# YF-Buzzer.net
KiCad netlist of a schematic drawn in EAGLE
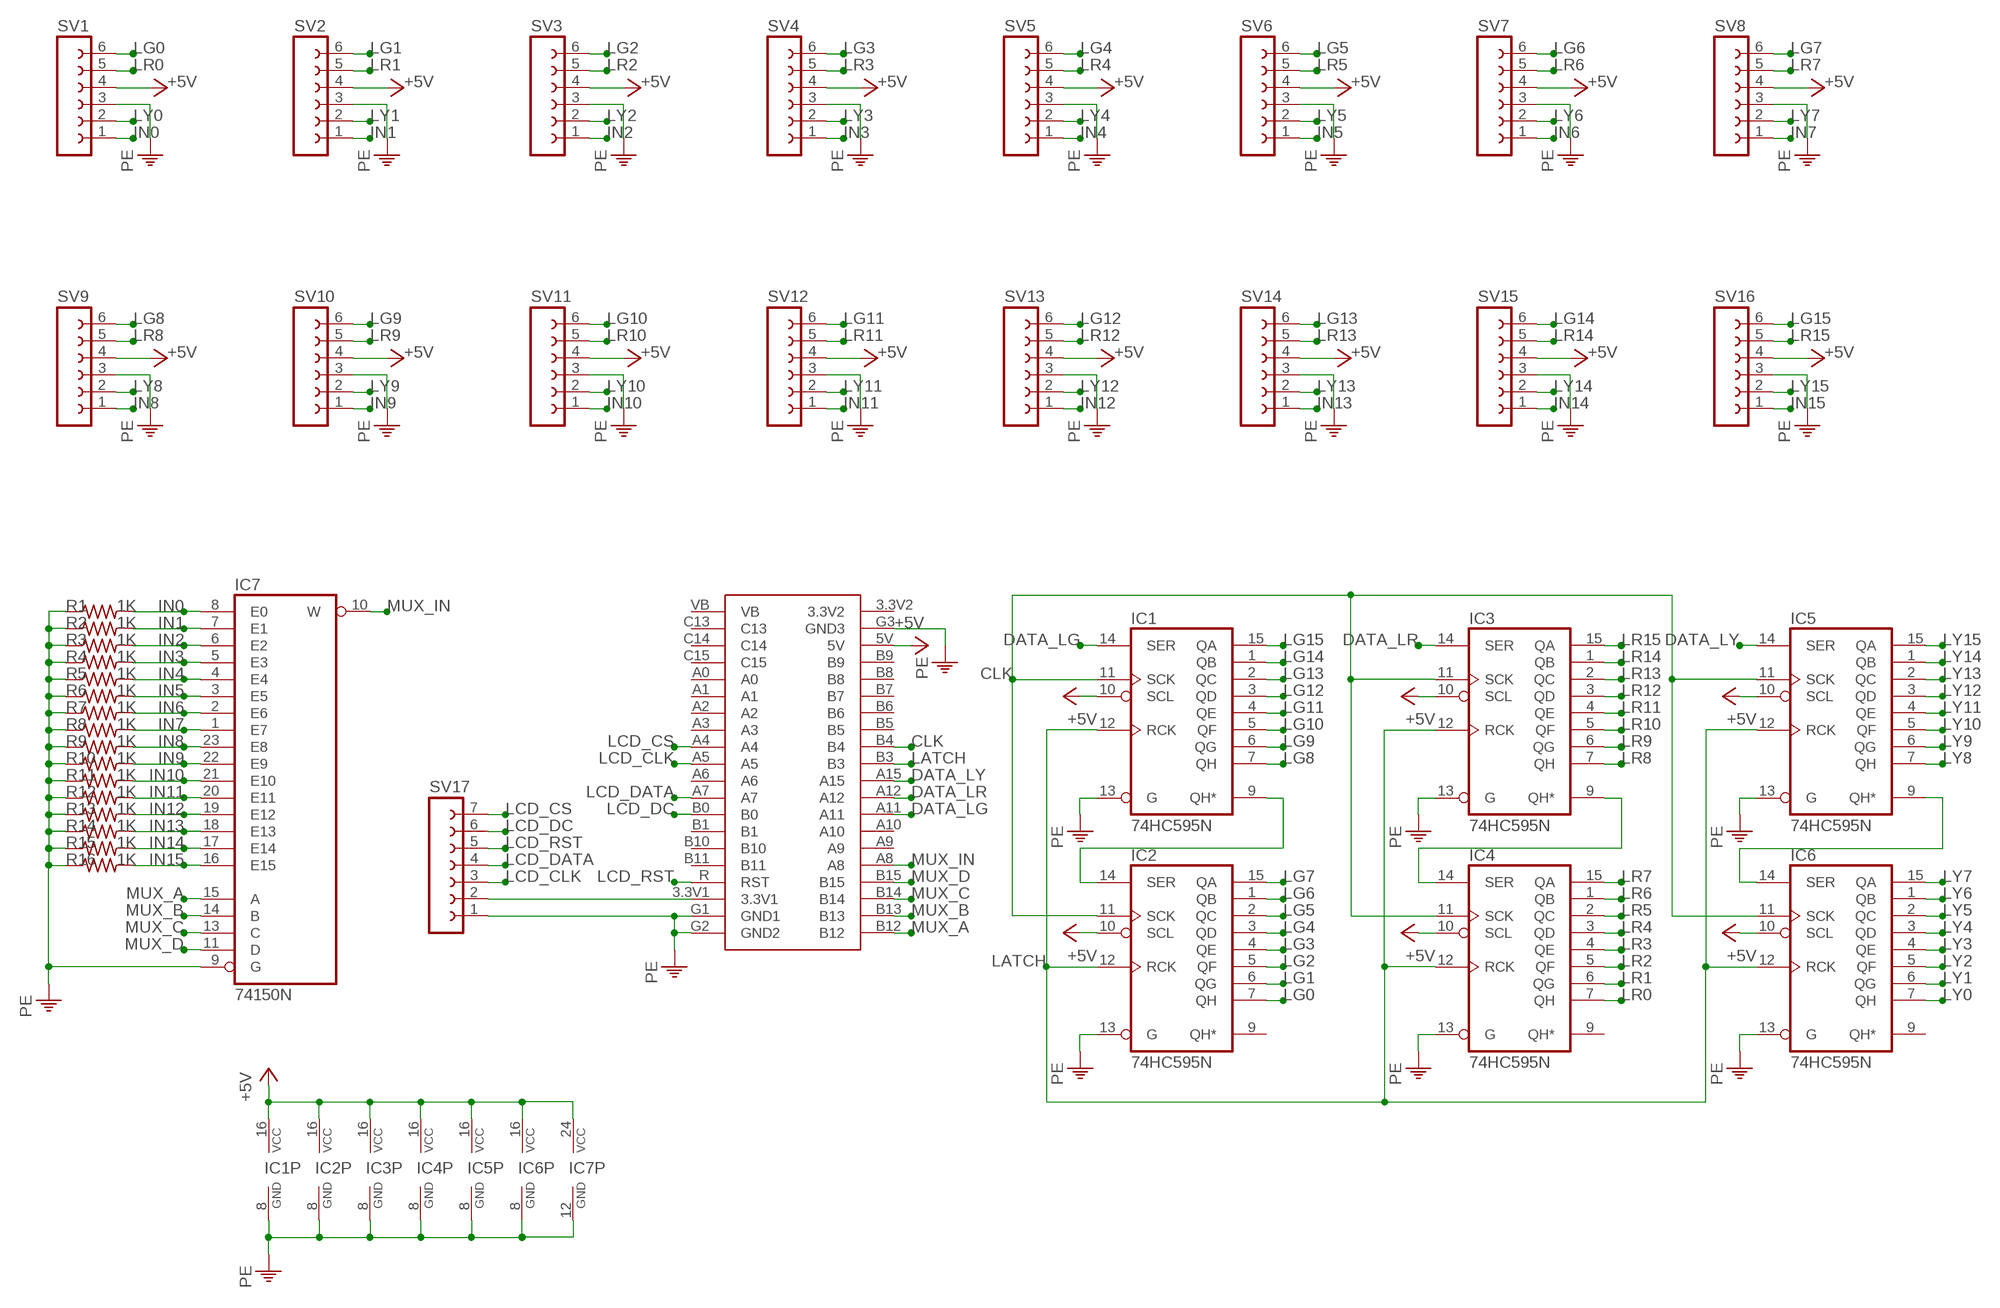
[diagram p0: schematic, sheet 1]

(export (version "E")
  (design (tool "Eeschema 10.0.6"))
  (components
    (comp (ref "IC1")
      (value "74HC595N")
      (footprint "eagle-import:DIL16")
      (libsource (lib "eagle-import") (part "74595NHC"))
    )
    (comp (ref "IC2")
      (value "74HC595N")
      (footprint "eagle-import:DIL16")
      (libsource (lib "eagle-import") (part "74595NHC"))
    )
    (comp (ref "IC3")
      (value "74HC595N")
      (footprint "eagle-import:DIL16")
      (libsource (lib "eagle-import") (part "74595NHC"))
    )
    (comp (ref "IC4")
      (value "74HC595N")
      (footprint "eagle-import:DIL16")
      (libsource (lib "eagle-import") (part "74595NHC"))
    )
    (comp (ref "IC5")
      (value "74HC595N")
      (footprint "eagle-import:DIL16")
      (libsource (lib "eagle-import") (part "74595NHC"))
    )
    (comp (ref "IC6")
      (value "74HC595N")
      (footprint "eagle-import:DIL16")
      (libsource (lib "eagle-import") (part "74595NHC"))
    )
    (comp (ref "IC7")
      (value "74150N")
      (footprint "eagle-import:DIL24-6")
      (libsource (lib "eagle-import") (part "74150N"))
    )
    (comp (ref "MCU1")
      (value "STM32-BLUE")
      (footprint "eagle-import:STM32-BLUE")
      (libsource (lib "eagle-import") (part "STM32-BLUE"))
    )
    (comp (ref "R1")
      (value "1K")
      (footprint "eagle-import:0207_10")
      (libsource (lib "eagle-import") (part "R-US_0207/10"))
    )
    (comp (ref "R2")
      (value "1K")
      (footprint "eagle-import:0207_10")
      (libsource (lib "eagle-import") (part "R-US_0207/10"))
    )
    (comp (ref "R3")
      (value "1K")
      (footprint "eagle-import:0207_10")
      (libsource (lib "eagle-import") (part "R-US_0207/10"))
    )
    (comp (ref "R4")
      (value "1K")
      (footprint "eagle-import:0207_10")
      (libsource (lib "eagle-import") (part "R-US_0207/10"))
    )
    (comp (ref "R5")
      (value "1K")
      (footprint "eagle-import:0207_10")
      (libsource (lib "eagle-import") (part "R-US_0207/10"))
    )
    (comp (ref "R6")
      (value "1K")
      (footprint "eagle-import:0207_10")
      (libsource (lib "eagle-import") (part "R-US_0207/10"))
    )
    (comp (ref "R7")
      (value "1K")
      (footprint "eagle-import:0207_10")
      (libsource (lib "eagle-import") (part "R-US_0207/10"))
    )
    (comp (ref "R8")
      (value "1K")
      (footprint "eagle-import:0207_10")
      (libsource (lib "eagle-import") (part "R-US_0207/10"))
    )
    (comp (ref "R9")
      (value "1K")
      (footprint "eagle-import:0207_10")
      (libsource (lib "eagle-import") (part "R-US_0207/10"))
    )
    (comp (ref "R10")
      (value "1K")
      (footprint "eagle-import:0207_10")
      (libsource (lib "eagle-import") (part "R-US_0207/10"))
    )
    (comp (ref "R11")
      (value "1K")
      (footprint "eagle-import:0207_10")
      (libsource (lib "eagle-import") (part "R-US_0207/10"))
    )
    (comp (ref "R12")
      (value "1K")
      (footprint "eagle-import:0207_10")
      (libsource (lib "eagle-import") (part "R-US_0207/10"))
    )
    (comp (ref "R13")
      (value "1K")
      (footprint "eagle-import:0207_10")
      (libsource (lib "eagle-import") (part "R-US_0207/10"))
    )
    (comp (ref "R14")
      (value "1K")
      (footprint "eagle-import:0207_10")
      (libsource (lib "eagle-import") (part "R-US_0207/10"))
    )
    (comp (ref "R15")
      (value "1K")
      (footprint "eagle-import:0207_10")
      (libsource (lib "eagle-import") (part "R-US_0207/10"))
    )
    (comp (ref "R16")
      (value "1K")
      (footprint "eagle-import:0207_10")
      (libsource (lib "eagle-import") (part "R-US_0207/10"))
    )
    (comp (ref "SV1")
      (value "FE06-1")
      (footprint "eagle-import:FE06")
      (libsource (lib "eagle-import") (part "FE06-1"))
    )
    (comp (ref "SV2")
      (value "FE06-1")
      (footprint "eagle-import:FE06")
      (libsource (lib "eagle-import") (part "FE06-1"))
    )
    (comp (ref "SV3")
      (value "FE06-1")
      (footprint "eagle-import:FE06")
      (libsource (lib "eagle-import") (part "FE06-1"))
    )
    (comp (ref "SV4")
      (value "FE06-1")
      (footprint "eagle-import:FE06")
      (libsource (lib "eagle-import") (part "FE06-1"))
    )
    (comp (ref "SV5")
      (value "FE06-1")
      (footprint "eagle-import:FE06")
      (libsource (lib "eagle-import") (part "FE06-1"))
    )
    (comp (ref "SV6")
      (value "FE06-1")
      (footprint "eagle-import:FE06")
      (libsource (lib "eagle-import") (part "FE06-1"))
    )
    (comp (ref "SV7")
      (value "FE06-1")
      (footprint "eagle-import:FE06")
      (libsource (lib "eagle-import") (part "FE06-1"))
    )
    (comp (ref "SV8")
      (value "FE06-1")
      (footprint "eagle-import:FE06")
      (libsource (lib "eagle-import") (part "FE06-1"))
    )
    (comp (ref "SV9")
      (value "FE06-1")
      (footprint "eagle-import:FE06")
      (libsource (lib "eagle-import") (part "FE06-1"))
    )
    (comp (ref "SV10")
      (value "FE06-1")
      (footprint "eagle-import:FE06")
      (libsource (lib "eagle-import") (part "FE06-1"))
    )
    (comp (ref "SV11")
      (value "FE06-1")
      (footprint "eagle-import:FE06")
      (libsource (lib "eagle-import") (part "FE06-1"))
    )
    (comp (ref "SV12")
      (value "FE06-1")
      (footprint "eagle-import:FE06")
      (libsource (lib "eagle-import") (part "FE06-1"))
    )
    (comp (ref "SV13")
      (value "FE06-1")
      (footprint "eagle-import:FE06")
      (libsource (lib "eagle-import") (part "FE06-1"))
    )
    (comp (ref "SV14")
      (value "FE06-1")
      (footprint "eagle-import:FE06")
      (libsource (lib "eagle-import") (part "FE06-1"))
    )
    (comp (ref "SV15")
      (value "FE06-1")
      (footprint "eagle-import:FE06")
      (libsource (lib "eagle-import") (part "FE06-1"))
    )
    (comp (ref "SV16")
      (value "FE06-1")
      (footprint "eagle-import:FE06")
      (libsource (lib "eagle-import") (part "FE06-1"))
    )
    (comp (ref "SV17")
      (value "FE07-1")
      (footprint "eagle-import:FE07")
      (libsource (lib "eagle-import") (part "FE07-1"))
    )
  )
  (nets
    (net (code "1") (name "+5V") (class "Default")
      (node (ref "IC1") (pin "10") (pinfunction "SCL_10") (pintype "input"))
      (node (ref "IC1") (pin "16") (pinfunction "VCC_16") (pintype "power_in"))
      (node (ref "IC2") (pin "10") (pinfunction "SCL_10") (pintype "input"))
      (node (ref "IC2") (pin "16") (pinfunction "VCC_16") (pintype "power_in"))
      (node (ref "IC3") (pin "10") (pinfunction "SCL_10") (pintype "input"))
      (node (ref "IC3") (pin "16") (pinfunction "VCC_16") (pintype "power_in"))
      (node (ref "IC4") (pin "10") (pinfunction "SCL_10") (pintype "input"))
      (node (ref "IC4") (pin "16") (pinfunction "VCC_16") (pintype "power_in"))
      (node (ref "IC5") (pin "10") (pinfunction "SCL_10") (pintype "input"))
      (node (ref "IC5") (pin "16") (pinfunction "VCC_16") (pintype "power_in"))
      (node (ref "IC6") (pin "10") (pinfunction "SCL_10") (pintype "input"))
      (node (ref "IC6") (pin "16") (pinfunction "VCC_16") (pintype "power_in"))
      (node (ref "IC7") (pin "24") (pinfunction "VCC_24") (pintype "power_in"))
      (node (ref "MCU1") (pin "5V") (pinfunction "5V_5V") (pintype "power_in"))
      (node (ref "SV1") (pin "4") (pinfunction "4_4") (pintype "passive"))
      (node (ref "SV10") (pin "4") (pinfunction "4_4") (pintype "passive"))
      (node (ref "SV11") (pin "4") (pinfunction "4_4") (pintype "passive"))
      (node (ref "SV12") (pin "4") (pinfunction "4_4") (pintype "passive"))
      (node (ref "SV13") (pin "4") (pinfunction "4_4") (pintype "passive"))
      (node (ref "SV14") (pin "4") (pinfunction "4_4") (pintype "passive"))
      (node (ref "SV15") (pin "4") (pinfunction "4_4") (pintype "passive"))
      (node (ref "SV16") (pin "4") (pinfunction "4_4") (pintype "passive"))
      (node (ref "SV2") (pin "4") (pinfunction "4_4") (pintype "passive"))
      (node (ref "SV3") (pin "4") (pinfunction "4_4") (pintype "passive"))
      (node (ref "SV4") (pin "4") (pinfunction "4_4") (pintype "passive"))
      (node (ref "SV5") (pin "4") (pinfunction "4_4") (pintype "passive"))
      (node (ref "SV6") (pin "4") (pinfunction "4_4") (pintype "passive"))
      (node (ref "SV7") (pin "4") (pinfunction "4_4") (pintype "passive"))
      (node (ref "SV8") (pin "4") (pinfunction "4_4") (pintype "passive"))
      (node (ref "SV9") (pin "4") (pinfunction "4_4") (pintype "passive"))
    )
    (net (code "2") (name "/3.3V2") (class "Default")
      (node (ref "MCU1") (pin "3.3V2") (pinfunction "3.3V2_3.3V2") (pintype "power_in"))
    )
    (net (code "3") (name "/CLK") (class "Default")
      (node (ref "IC1") (pin "11") (pinfunction "SCK_11") (pintype "input"))
      (node (ref "IC2") (pin "11") (pinfunction "SCK_11") (pintype "input"))
      (node (ref "IC3") (pin "11") (pinfunction "SCK_11") (pintype "input"))
      (node (ref "IC4") (pin "11") (pinfunction "SCK_11") (pintype "input"))
      (node (ref "IC5") (pin "11") (pinfunction "SCK_11") (pintype "input"))
      (node (ref "IC6") (pin "11") (pinfunction "SCK_11") (pintype "input"))
      (node (ref "MCU1") (pin "B4") (pinfunction "B4_B4") (pintype "bidirectional"))
    )
    (net (code "4") (name "/DATA_LG") (class "Default")
      (node (ref "IC1") (pin "14") (pinfunction "SER_14") (pintype "input"))
      (node (ref "MCU1") (pin "A11") (pinfunction "A11_A11") (pintype "bidirectional"))
    )
    (net (code "5") (name "/DATA_LR") (class "Default")
      (node (ref "IC3") (pin "14") (pinfunction "SER_14") (pintype "input"))
      (node (ref "MCU1") (pin "A12") (pinfunction "A12_A12") (pintype "bidirectional"))
    )
    (net (code "6") (name "/DATA_LY") (class "Default")
      (node (ref "IC5") (pin "14") (pinfunction "SER_14") (pintype "input"))
      (node (ref "MCU1") (pin "A15") (pinfunction "A15_A15") (pintype "bidirectional"))
    )
    (net (code "7") (name "/IN0") (class "Default")
      (node (ref "IC7") (pin "8") (pinfunction "E0_8") (pintype "input"))
      (node (ref "R1") (pin "2") (pinfunction "2_2") (pintype "passive"))
      (node (ref "SV1") (pin "1") (pinfunction "1_1") (pintype "passive"))
    )
    (net (code "8") (name "/IN1") (class "Default")
      (node (ref "IC7") (pin "7") (pinfunction "E1_7") (pintype "input"))
      (node (ref "R2") (pin "2") (pinfunction "2_2") (pintype "passive"))
      (node (ref "SV2") (pin "1") (pinfunction "1_1") (pintype "passive"))
    )
    (net (code "9") (name "/IN2") (class "Default")
      (node (ref "IC7") (pin "6") (pinfunction "E2_6") (pintype "input"))
      (node (ref "R3") (pin "2") (pinfunction "2_2") (pintype "passive"))
      (node (ref "SV3") (pin "1") (pinfunction "1_1") (pintype "passive"))
    )
    (net (code "10") (name "/IN3") (class "Default")
      (node (ref "IC7") (pin "5") (pinfunction "E3_5") (pintype "input"))
      (node (ref "R4") (pin "2") (pinfunction "2_2") (pintype "passive"))
      (node (ref "SV4") (pin "1") (pinfunction "1_1") (pintype "passive"))
    )
    (net (code "11") (name "/IN4") (class "Default")
      (node (ref "IC7") (pin "4") (pinfunction "E4_4") (pintype "input"))
      (node (ref "R5") (pin "2") (pinfunction "2_2") (pintype "passive"))
      (node (ref "SV5") (pin "1") (pinfunction "1_1") (pintype "passive"))
    )
    (net (code "12") (name "/IN5") (class "Default")
      (node (ref "IC7") (pin "3") (pinfunction "E5_3") (pintype "input"))
      (node (ref "R6") (pin "2") (pinfunction "2_2") (pintype "passive"))
      (node (ref "SV6") (pin "1") (pinfunction "1_1") (pintype "passive"))
    )
    (net (code "13") (name "/IN6") (class "Default")
      (node (ref "IC7") (pin "2") (pinfunction "E6_2") (pintype "input"))
      (node (ref "R7") (pin "2") (pinfunction "2_2") (pintype "passive"))
      (node (ref "SV7") (pin "1") (pinfunction "1_1") (pintype "passive"))
    )
    (net (code "14") (name "/IN7") (class "Default")
      (node (ref "IC7") (pin "1") (pinfunction "E7_1") (pintype "input"))
      (node (ref "R8") (pin "2") (pinfunction "2_2") (pintype "passive"))
      (node (ref "SV8") (pin "1") (pinfunction "1_1") (pintype "passive"))
    )
    (net (code "15") (name "/IN8") (class "Default")
      (node (ref "IC7") (pin "23") (pinfunction "E8_23") (pintype "input"))
      (node (ref "R9") (pin "2") (pinfunction "2_2") (pintype "passive"))
      (node (ref "SV9") (pin "1") (pinfunction "1_1") (pintype "passive"))
    )
    (net (code "16") (name "/IN9") (class "Default")
      (node (ref "IC7") (pin "22") (pinfunction "E9_22") (pintype "input"))
      (node (ref "R10") (pin "2") (pinfunction "2_2") (pintype "passive"))
      (node (ref "SV10") (pin "1") (pinfunction "1_1") (pintype "passive"))
    )
    (net (code "17") (name "/IN10") (class "Default")
      (node (ref "IC7") (pin "21") (pinfunction "E10_21") (pintype "input"))
      (node (ref "R11") (pin "2") (pinfunction "2_2") (pintype "passive"))
      (node (ref "SV11") (pin "1") (pinfunction "1_1") (pintype "passive"))
    )
    (net (code "18") (name "/IN11") (class "Default")
      (node (ref "IC7") (pin "20") (pinfunction "E11_20") (pintype "input"))
      (node (ref "R12") (pin "2") (pinfunction "2_2") (pintype "passive"))
      (node (ref "SV12") (pin "1") (pinfunction "1_1") (pintype "passive"))
    )
    (net (code "19") (name "/IN12") (class "Default")
      (node (ref "IC7") (pin "19") (pinfunction "E12_19") (pintype "input"))
      (node (ref "R13") (pin "2") (pinfunction "2_2") (pintype "passive"))
      (node (ref "SV13") (pin "1") (pinfunction "1_1") (pintype "passive"))
    )
    (net (code "20") (name "/IN13") (class "Default")
      (node (ref "IC7") (pin "18") (pinfunction "E13_18") (pintype "input"))
      (node (ref "R14") (pin "2") (pinfunction "2_2") (pintype "passive"))
      (node (ref "SV14") (pin "1") (pinfunction "1_1") (pintype "passive"))
    )
    (net (code "21") (name "/IN14") (class "Default")
      (node (ref "IC7") (pin "17") (pinfunction "E14_17") (pintype "input"))
      (node (ref "R15") (pin "2") (pinfunction "2_2") (pintype "passive"))
      (node (ref "SV15") (pin "1") (pinfunction "1_1") (pintype "passive"))
    )
    (net (code "22") (name "/IN15") (class "Default")
      (node (ref "IC7") (pin "16") (pinfunction "E15_16") (pintype "input"))
      (node (ref "R16") (pin "2") (pinfunction "2_2") (pintype "passive"))
      (node (ref "SV16") (pin "1") (pinfunction "1_1") (pintype "passive"))
    )
    (net (code "23") (name "/LATCH") (class "Default")
      (node (ref "IC1") (pin "12") (pinfunction "RCK_12") (pintype "input"))
      (node (ref "IC2") (pin "12") (pinfunction "RCK_12") (pintype "input"))
      (node (ref "IC3") (pin "12") (pinfunction "RCK_12") (pintype "input"))
      (node (ref "IC4") (pin "12") (pinfunction "RCK_12") (pintype "input"))
      (node (ref "IC5") (pin "12") (pinfunction "RCK_12") (pintype "input"))
      (node (ref "IC6") (pin "12") (pinfunction "RCK_12") (pintype "input"))
      (node (ref "MCU1") (pin "B3") (pinfunction "B3_B3") (pintype "bidirectional"))
    )
    (net (code "24") (name "/LCD_CLK") (class "Default")
      (node (ref "MCU1") (pin "A5") (pinfunction "A5_A5") (pintype "bidirectional"))
      (node (ref "SV17") (pin "3") (pinfunction "3_3") (pintype "passive"))
    )
    (net (code "25") (name "/LCD_CS") (class "Default")
      (node (ref "MCU1") (pin "A4") (pinfunction "A4_A4") (pintype "bidirectional"))
      (node (ref "SV17") (pin "7") (pinfunction "7_7") (pintype "passive"))
    )
    (net (code "26") (name "/LCD_DATA") (class "Default")
      (node (ref "MCU1") (pin "A7") (pinfunction "A7_A7") (pintype "bidirectional"))
      (node (ref "SV17") (pin "4") (pinfunction "4_4") (pintype "passive"))
    )
    (net (code "27") (name "/LCD_DC") (class "Default")
      (node (ref "MCU1") (pin "B0") (pinfunction "B0_B0") (pintype "bidirectional"))
      (node (ref "SV17") (pin "6") (pinfunction "6_6") (pintype "passive"))
    )
    (net (code "28") (name "/LCD_RST") (class "Default")
      (node (ref "MCU1") (pin "R") (pinfunction "RST_R") (pintype "bidirectional"))
      (node (ref "SV17") (pin "5") (pinfunction "5_5") (pintype "passive"))
    )
    (net (code "29") (name "/LG0") (class "Default")
      (node (ref "IC2") (pin "7") (pinfunction "QH_7") (pintype "tri_state"))
      (node (ref "SV1") (pin "6") (pinfunction "6_6") (pintype "passive"))
    )
    (net (code "30") (name "/LG1") (class "Default")
      (node (ref "IC2") (pin "6") (pinfunction "QG_6") (pintype "tri_state"))
      (node (ref "SV2") (pin "6") (pinfunction "6_6") (pintype "passive"))
    )
    (net (code "31") (name "/LG2") (class "Default")
      (node (ref "IC2") (pin "5") (pinfunction "QF_5") (pintype "tri_state"))
      (node (ref "SV3") (pin "6") (pinfunction "6_6") (pintype "passive"))
    )
    (net (code "32") (name "/LG3") (class "Default")
      (node (ref "IC2") (pin "4") (pinfunction "QE_4") (pintype "tri_state"))
      (node (ref "SV4") (pin "6") (pinfunction "6_6") (pintype "passive"))
    )
    (net (code "33") (name "/LG4") (class "Default")
      (node (ref "IC2") (pin "3") (pinfunction "QD_3") (pintype "tri_state"))
      (node (ref "SV5") (pin "6") (pinfunction "6_6") (pintype "passive"))
    )
    (net (code "34") (name "/LG5") (class "Default")
      (node (ref "IC2") (pin "2") (pinfunction "QC_2") (pintype "tri_state"))
      (node (ref "SV6") (pin "6") (pinfunction "6_6") (pintype "passive"))
    )
    (net (code "35") (name "/LG6") (class "Default")
      (node (ref "IC2") (pin "1") (pinfunction "QB_1") (pintype "tri_state"))
      (node (ref "SV7") (pin "6") (pinfunction "6_6") (pintype "passive"))
    )
    (net (code "36") (name "/LG7") (class "Default")
      (node (ref "IC2") (pin "15") (pinfunction "QA_15") (pintype "tri_state"))
      (node (ref "SV8") (pin "6") (pinfunction "6_6") (pintype "passive"))
    )
    (net (code "37") (name "/LG8") (class "Default")
      (node (ref "IC1") (pin "7") (pinfunction "QH_7") (pintype "tri_state"))
      (node (ref "SV9") (pin "6") (pinfunction "6_6") (pintype "passive"))
    )
    (net (code "38") (name "/LG9") (class "Default")
      (node (ref "IC1") (pin "6") (pinfunction "QG_6") (pintype "tri_state"))
      (node (ref "SV10") (pin "6") (pinfunction "6_6") (pintype "passive"))
    )
    (net (code "39") (name "/LG10") (class "Default")
      (node (ref "IC1") (pin "5") (pinfunction "QF_5") (pintype "tri_state"))
      (node (ref "SV11") (pin "6") (pinfunction "6_6") (pintype "passive"))
    )
    (net (code "40") (name "/LG11") (class "Default")
      (node (ref "IC1") (pin "4") (pinfunction "QE_4") (pintype "tri_state"))
      (node (ref "SV12") (pin "6") (pinfunction "6_6") (pintype "passive"))
    )
    (net (code "41") (name "/LG12") (class "Default")
      (node (ref "IC1") (pin "3") (pinfunction "QD_3") (pintype "tri_state"))
      (node (ref "SV13") (pin "6") (pinfunction "6_6") (pintype "passive"))
    )
    (net (code "42") (name "/LG13") (class "Default")
      (node (ref "IC1") (pin "2") (pinfunction "QC_2") (pintype "tri_state"))
      (node (ref "SV14") (pin "6") (pinfunction "6_6") (pintype "passive"))
    )
    (net (code "43") (name "/LG14") (class "Default")
      (node (ref "IC1") (pin "1") (pinfunction "QB_1") (pintype "tri_state"))
      (node (ref "SV15") (pin "6") (pinfunction "6_6") (pintype "passive"))
    )
    (net (code "44") (name "/LG15") (class "Default")
      (node (ref "IC1") (pin "15") (pinfunction "QA_15") (pintype "tri_state"))
      (node (ref "SV16") (pin "6") (pinfunction "6_6") (pintype "passive"))
    )
    (net (code "45") (name "/LR0") (class "Default")
      (node (ref "IC4") (pin "7") (pinfunction "QH_7") (pintype "tri_state"))
      (node (ref "SV1") (pin "5") (pinfunction "5_5") (pintype "passive"))
    )
    (net (code "46") (name "/LR1") (class "Default")
      (node (ref "IC4") (pin "6") (pinfunction "QG_6") (pintype "tri_state"))
      (node (ref "SV2") (pin "5") (pinfunction "5_5") (pintype "passive"))
    )
    (net (code "47") (name "/LR2") (class "Default")
      (node (ref "IC4") (pin "5") (pinfunction "QF_5") (pintype "tri_state"))
      (node (ref "SV3") (pin "5") (pinfunction "5_5") (pintype "passive"))
    )
    (net (code "48") (name "/LR3") (class "Default")
      (node (ref "IC4") (pin "4") (pinfunction "QE_4") (pintype "tri_state"))
      (node (ref "SV4") (pin "5") (pinfunction "5_5") (pintype "passive"))
    )
    (net (code "49") (name "/LR4") (class "Default")
      (node (ref "IC4") (pin "3") (pinfunction "QD_3") (pintype "tri_state"))
      (node (ref "SV5") (pin "5") (pinfunction "5_5") (pintype "passive"))
    )
    (net (code "50") (name "/LR5") (class "Default")
      (node (ref "IC4") (pin "2") (pinfunction "QC_2") (pintype "tri_state"))
      (node (ref "SV6") (pin "5") (pinfunction "5_5") (pintype "passive"))
    )
    (net (code "51") (name "/LR6") (class "Default")
      (node (ref "IC4") (pin "1") (pinfunction "QB_1") (pintype "tri_state"))
      (node (ref "SV7") (pin "5") (pinfunction "5_5") (pintype "passive"))
    )
    (net (code "52") (name "/LR7") (class "Default")
      (node (ref "IC4") (pin "15") (pinfunction "QA_15") (pintype "tri_state"))
      (node (ref "SV8") (pin "5") (pinfunction "5_5") (pintype "passive"))
    )
    (net (code "53") (name "/LR8") (class "Default")
      (node (ref "IC3") (pin "7") (pinfunction "QH_7") (pintype "tri_state"))
      (node (ref "SV9") (pin "5") (pinfunction "5_5") (pintype "passive"))
    )
    (net (code "54") (name "/LR9") (class "Default")
      (node (ref "IC3") (pin "6") (pinfunction "QG_6") (pintype "tri_state"))
      (node (ref "SV10") (pin "5") (pinfunction "5_5") (pintype "passive"))
    )
    (net (code "55") (name "/LR10") (class "Default")
      (node (ref "IC3") (pin "5") (pinfunction "QF_5") (pintype "tri_state"))
      (node (ref "SV11") (pin "5") (pinfunction "5_5") (pintype "passive"))
    )
    (net (code "56") (name "/LR11") (class "Default")
      (node (ref "IC3") (pin "4") (pinfunction "QE_4") (pintype "tri_state"))
      (node (ref "SV12") (pin "5") (pinfunction "5_5") (pintype "passive"))
    )
    (net (code "57") (name "/LR12") (class "Default")
      (node (ref "IC3") (pin "3") (pinfunction "QD_3") (pintype "tri_state"))
      (node (ref "SV13") (pin "5") (pinfunction "5_5") (pintype "passive"))
    )
    (net (code "58") (name "/LR13") (class "Default")
      (node (ref "IC3") (pin "2") (pinfunction "QC_2") (pintype "tri_state"))
      (node (ref "SV14") (pin "5") (pinfunction "5_5") (pintype "passive"))
    )
    (net (code "59") (name "/LR14") (class "Default")
      (node (ref "IC3") (pin "1") (pinfunction "QB_1") (pintype "tri_state"))
      (node (ref "SV15") (pin "5") (pinfunction "5_5") (pintype "passive"))
    )
    (net (code "60") (name "/LR15") (class "Default")
      (node (ref "IC3") (pin "15") (pinfunction "QA_15") (pintype "tri_state"))
      (node (ref "SV16") (pin "5") (pinfunction "5_5") (pintype "passive"))
    )
    (net (code "61") (name "/LY0") (class "Default")
      (node (ref "IC6") (pin "7") (pinfunction "QH_7") (pintype "tri_state"))
      (node (ref "SV1") (pin "2") (pinfunction "2_2") (pintype "passive"))
    )
    (net (code "62") (name "/LY1") (class "Default")
      (node (ref "IC6") (pin "6") (pinfunction "QG_6") (pintype "tri_state"))
      (node (ref "SV2") (pin "2") (pinfunction "2_2") (pintype "passive"))
    )
    (net (code "63") (name "/LY2") (class "Default")
      (node (ref "IC6") (pin "5") (pinfunction "QF_5") (pintype "tri_state"))
      (node (ref "SV3") (pin "2") (pinfunction "2_2") (pintype "passive"))
    )
    (net (code "64") (name "/LY3") (class "Default")
      (node (ref "IC6") (pin "4") (pinfunction "QE_4") (pintype "tri_state"))
      (node (ref "SV4") (pin "2") (pinfunction "2_2") (pintype "passive"))
    )
    (net (code "65") (name "/LY4") (class "Default")
      (node (ref "IC6") (pin "3") (pinfunction "QD_3") (pintype "tri_state"))
      (node (ref "SV5") (pin "2") (pinfunction "2_2") (pintype "passive"))
    )
    (net (code "66") (name "/LY5") (class "Default")
      (node (ref "IC6") (pin "2") (pinfunction "QC_2") (pintype "tri_state"))
      (node (ref "SV6") (pin "2") (pinfunction "2_2") (pintype "passive"))
    )
    (net (code "67") (name "/LY6") (class "Default")
      (node (ref "IC6") (pin "1") (pinfunction "QB_1") (pintype "tri_state"))
      (node (ref "SV7") (pin "2") (pinfunction "2_2") (pintype "passive"))
    )
    (net (code "68") (name "/LY7") (class "Default")
      (node (ref "IC6") (pin "15") (pinfunction "QA_15") (pintype "tri_state"))
      (node (ref "SV8") (pin "2") (pinfunction "2_2") (pintype "passive"))
    )
    (net (code "69") (name "/LY8") (class "Default")
      (node (ref "IC5") (pin "7") (pinfunction "QH_7") (pintype "tri_state"))
      (node (ref "SV9") (pin "2") (pinfunction "2_2") (pintype "passive"))
    )
    (net (code "70") (name "/LY9") (class "Default")
      (node (ref "IC5") (pin "6") (pinfunction "QG_6") (pintype "tri_state"))
      (node (ref "SV10") (pin "2") (pinfunction "2_2") (pintype "passive"))
    )
    (net (code "71") (name "/LY10") (class "Default")
      (node (ref "IC5") (pin "5") (pinfunction "QF_5") (pintype "tri_state"))
      (node (ref "SV11") (pin "2") (pinfunction "2_2") (pintype "passive"))
    )
    (net (code "72") (name "/LY11") (class "Default")
      (node (ref "IC5") (pin "4") (pinfunction "QE_4") (pintype "tri_state"))
      (node (ref "SV12") (pin "2") (pinfunction "2_2") (pintype "passive"))
    )
    (net (code "73") (name "/LY12") (class "Default")
      (node (ref "IC5") (pin "3") (pinfunction "QD_3") (pintype "tri_state"))
      (node (ref "SV13") (pin "2") (pinfunction "2_2") (pintype "passive"))
    )
    (net (code "74") (name "/LY13") (class "Default")
      (node (ref "IC5") (pin "2") (pinfunction "QC_2") (pintype "tri_state"))
      (node (ref "SV14") (pin "2") (pinfunction "2_2") (pintype "passive"))
    )
    (net (code "75") (name "/LY14") (class "Default")
      (node (ref "IC5") (pin "1") (pinfunction "QB_1") (pintype "tri_state"))
      (node (ref "SV15") (pin "2") (pinfunction "2_2") (pintype "passive"))
    )
    (net (code "76") (name "/LY15") (class "Default")
      (node (ref "IC5") (pin "15") (pinfunction "QA_15") (pintype "tri_state"))
      (node (ref "SV16") (pin "2") (pinfunction "2_2") (pintype "passive"))
    )
    (net (code "77") (name "/MUX_A") (class "Default")
      (node (ref "IC7") (pin "15") (pinfunction "A_15") (pintype "input"))
      (node (ref "MCU1") (pin "B12") (pinfunction "B12_B12") (pintype "bidirectional"))
    )
    (net (code "78") (name "/MUX_B") (class "Default")
      (node (ref "IC7") (pin "14") (pinfunction "B_14") (pintype "input"))
      (node (ref "MCU1") (pin "B13") (pinfunction "B13_B13") (pintype "bidirectional"))
    )
    (net (code "79") (name "/MUX_C") (class "Default")
      (node (ref "IC7") (pin "13") (pinfunction "C_13") (pintype "input"))
      (node (ref "MCU1") (pin "B14") (pinfunction "B14_B14") (pintype "bidirectional"))
    )
    (net (code "80") (name "/MUX_D") (class "Default")
      (node (ref "IC7") (pin "11") (pinfunction "D_11") (pintype "input"))
      (node (ref "MCU1") (pin "B15") (pinfunction "B15_B15") (pintype "bidirectional"))
    )
    (net (code "81") (name "/MUX_IN") (class "Default")
      (node (ref "IC7") (pin "10") (pinfunction "W_10") (pintype "output"))
      (node (ref "MCU1") (pin "A8") (pinfunction "A8_A8") (pintype "bidirectional"))
    )
    (net (code "82") (name "/VB") (class "Default")
      (node (ref "MCU1") (pin "VB") (pinfunction "VB_VB") (pintype "power_in"))
    )
    (net (code "83") (name "Net-(IC1A-QH*)") (class "Default")
      (node (ref "IC1") (pin "9") (pinfunction "QH*_9") (pintype "tri_state"))
      (node (ref "IC2") (pin "14") (pinfunction "SER_14") (pintype "input"))
    )
    (net (code "84") (name "Net-(IC3A-QH*)") (class "Default")
      (node (ref "IC3") (pin "9") (pinfunction "QH*_9") (pintype "tri_state"))
      (node (ref "IC4") (pin "14") (pinfunction "SER_14") (pintype "input"))
    )
    (net (code "85") (name "Net-(IC5A-QH*)") (class "Default")
      (node (ref "IC5") (pin "9") (pinfunction "QH*_9") (pintype "tri_state"))
      (node (ref "IC6") (pin "14") (pinfunction "SER_14") (pintype "input"))
    )
    (net (code "86") (name "Net-(MCU1-Pad3.3V1)") (class "Default")
      (node (ref "MCU1") (pin "3.3V1") (pinfunction "3.3V1_3.3V1") (pintype "power_in"))
      (node (ref "SV17") (pin "2") (pinfunction "2_2") (pintype "passive"))
    )
    (net (code "87") (name "PE") (class "Default")
      (node (ref "IC1") (pin "13") (pinfunction "G_13") (pintype "input"))
      (node (ref "IC1") (pin "8") (pinfunction "GND_8") (pintype "power_in"))
      (node (ref "IC2") (pin "13") (pinfunction "G_13") (pintype "input"))
      (node (ref "IC2") (pin "8") (pinfunction "GND_8") (pintype "power_in"))
      (node (ref "IC3") (pin "13") (pinfunction "G_13") (pintype "input"))
      (node (ref "IC3") (pin "8") (pinfunction "GND_8") (pintype "power_in"))
      (node (ref "IC4") (pin "13") (pinfunction "G_13") (pintype "input"))
      (node (ref "IC4") (pin "8") (pinfunction "GND_8") (pintype "power_in"))
      (node (ref "IC5") (pin "13") (pinfunction "G_13") (pintype "input"))
      (node (ref "IC5") (pin "8") (pinfunction "GND_8") (pintype "power_in"))
      (node (ref "IC6") (pin "13") (pinfunction "G_13") (pintype "input"))
      (node (ref "IC6") (pin "8") (pinfunction "GND_8") (pintype "power_in"))
      (node (ref "IC7") (pin "12") (pinfunction "GND_12") (pintype "power_in"))
      (node (ref "IC7") (pin "9") (pinfunction "G_9") (pintype "input"))
      (node (ref "MCU1") (pin "G1") (pinfunction "GND1_G1") (pintype "power_in"))
      (node (ref "MCU1") (pin "G2") (pinfunction "GND2_G2") (pintype "power_in"))
      (node (ref "MCU1") (pin "G3") (pinfunction "GND3_G3") (pintype "power_in"))
      (node (ref "R1") (pin "1") (pinfunction "1_1") (pintype "passive"))
      (node (ref "R10") (pin "1") (pinfunction "1_1") (pintype "passive"))
      (node (ref "R11") (pin "1") (pinfunction "1_1") (pintype "passive"))
      (node (ref "R12") (pin "1") (pinfunction "1_1") (pintype "passive"))
      (node (ref "R13") (pin "1") (pinfunction "1_1") (pintype "passive"))
      (node (ref "R14") (pin "1") (pinfunction "1_1") (pintype "passive"))
      (node (ref "R15") (pin "1") (pinfunction "1_1") (pintype "passive"))
      (node (ref "R16") (pin "1") (pinfunction "1_1") (pintype "passive"))
      (node (ref "R2") (pin "1") (pinfunction "1_1") (pintype "passive"))
      (node (ref "R3") (pin "1") (pinfunction "1_1") (pintype "passive"))
      (node (ref "R4") (pin "1") (pinfunction "1_1") (pintype "passive"))
      (node (ref "R5") (pin "1") (pinfunction "1_1") (pintype "passive"))
      (node (ref "R6") (pin "1") (pinfunction "1_1") (pintype "passive"))
      (node (ref "R7") (pin "1") (pinfunction "1_1") (pintype "passive"))
      (node (ref "R8") (pin "1") (pinfunction "1_1") (pintype "passive"))
      (node (ref "R9") (pin "1") (pinfunction "1_1") (pintype "passive"))
      (node (ref "SV1") (pin "3") (pinfunction "3_3") (pintype "passive"))
      (node (ref "SV10") (pin "3") (pinfunction "3_3") (pintype "passive"))
      (node (ref "SV11") (pin "3") (pinfunction "3_3") (pintype "passive"))
      (node (ref "SV12") (pin "3") (pinfunction "3_3") (pintype "passive"))
      (node (ref "SV13") (pin "3") (pinfunction "3_3") (pintype "passive"))
      (node (ref "SV14") (pin "3") (pinfunction "3_3") (pintype "passive"))
      (node (ref "SV15") (pin "3") (pinfunction "3_3") (pintype "passive"))
      (node (ref "SV16") (pin "3") (pinfunction "3_3") (pintype "passive"))
      (node (ref "SV17") (pin "1") (pinfunction "1_1") (pintype "passive"))
      (node (ref "SV2") (pin "3") (pinfunction "3_3") (pintype "passive"))
      (node (ref "SV3") (pin "3") (pinfunction "3_3") (pintype "passive"))
      (node (ref "SV4") (pin "3") (pinfunction "3_3") (pintype "passive"))
      (node (ref "SV5") (pin "3") (pinfunction "3_3") (pintype "passive"))
      (node (ref "SV6") (pin "3") (pinfunction "3_3") (pintype "passive"))
      (node (ref "SV7") (pin "3") (pinfunction "3_3") (pintype "passive"))
      (node (ref "SV8") (pin "3") (pinfunction "3_3") (pintype "passive"))
      (node (ref "SV9") (pin "3") (pinfunction "3_3") (pintype "passive"))
    )
    (net (code "88") (name "unconnected-(IC2A-QH*-Pad9)") (class "Default")
      (node (ref "IC2") (pin "9") (pinfunction "QH*_9") (pintype "tri_state"))
    )
    (net (code "89") (name "unconnected-(IC4A-QH*-Pad9)") (class "Default")
      (node (ref "IC4") (pin "9") (pinfunction "QH*_9") (pintype "tri_state"))
    )
    (net (code "90") (name "unconnected-(IC6A-QH*-Pad9)") (class "Default")
      (node (ref "IC6") (pin "9") (pinfunction "QH*_9") (pintype "tri_state"))
    )
    (net (code "91") (name "unconnected-(MCU1-PadA0)") (class "Default")
      (node (ref "MCU1") (pin "A0") (pinfunction "A0_A0") (pintype "bidirectional"))
    )
    (net (code "92") (name "unconnected-(MCU1-PadA1)") (class "Default")
      (node (ref "MCU1") (pin "A1") (pinfunction "A1_A1") (pintype "bidirectional"))
    )
    (net (code "93") (name "unconnected-(MCU1-PadA2)") (class "Default")
      (node (ref "MCU1") (pin "A2") (pinfunction "A2_A2") (pintype "bidirectional"))
    )
    (net (code "94") (name "unconnected-(MCU1-PadA3)") (class "Default")
      (node (ref "MCU1") (pin "A3") (pinfunction "A3_A3") (pintype "bidirectional"))
    )
    (net (code "95") (name "unconnected-(MCU1-PadA6)") (class "Default")
      (node (ref "MCU1") (pin "A6") (pinfunction "A6_A6") (pintype "bidirectional"))
    )
    (net (code "96") (name "unconnected-(MCU1-PadA9)") (class "Default")
      (node (ref "MCU1") (pin "A9") (pinfunction "A9_A9") (pintype "bidirectional"))
    )
    (net (code "97") (name "unconnected-(MCU1-PadA10)") (class "Default")
      (node (ref "MCU1") (pin "A10") (pinfunction "A10_A10") (pintype "bidirectional"))
    )
    (net (code "98") (name "unconnected-(MCU1-PadB1)") (class "Default")
      (node (ref "MCU1") (pin "B1") (pinfunction "B1_B1") (pintype "bidirectional"))
    )
    (net (code "99") (name "unconnected-(MCU1-PadB5)") (class "Default")
      (node (ref "MCU1") (pin "B5") (pinfunction "B5_B5") (pintype "bidirectional"))
    )
    (net (code "100") (name "unconnected-(MCU1-PadB6)") (class "Default")
      (node (ref "MCU1") (pin "B6") (pinfunction "B6_B6") (pintype "bidirectional"))
    )
    (net (code "101") (name "unconnected-(MCU1-PadB7)") (class "Default")
      (node (ref "MCU1") (pin "B7") (pinfunction "B7_B7") (pintype "bidirectional"))
    )
    (net (code "102") (name "unconnected-(MCU1-PadB8)") (class "Default")
      (node (ref "MCU1") (pin "B8") (pinfunction "B8_B8") (pintype "bidirectional"))
    )
    (net (code "103") (name "unconnected-(MCU1-PadB9)") (class "Default")
      (node (ref "MCU1") (pin "B9") (pinfunction "B9_B9") (pintype "bidirectional"))
    )
    (net (code "104") (name "unconnected-(MCU1-PadB10)") (class "Default")
      (node (ref "MCU1") (pin "B10") (pinfunction "B10_B10") (pintype "bidirectional"))
    )
    (net (code "105") (name "unconnected-(MCU1-PadB11)") (class "Default")
      (node (ref "MCU1") (pin "B11") (pinfunction "B11_B11") (pintype "bidirectional"))
    )
    (net (code "106") (name "unconnected-(MCU1-PadC13)") (class "Default")
      (node (ref "MCU1") (pin "C13") (pinfunction "C13_C13") (pintype "bidirectional"))
    )
    (net (code "107") (name "unconnected-(MCU1-PadC14)") (class "Default")
      (node (ref "MCU1") (pin "C14") (pinfunction "C14_C14") (pintype "bidirectional"))
    )
    (net (code "108") (name "unconnected-(MCU1-PadC15)") (class "Default")
      (node (ref "MCU1") (pin "C15") (pinfunction "C15_C15") (pintype "bidirectional"))
    )
  )
)
